# AUDIO_DAC.net
KiCad netlist of a schematic drawn in Altium Designer
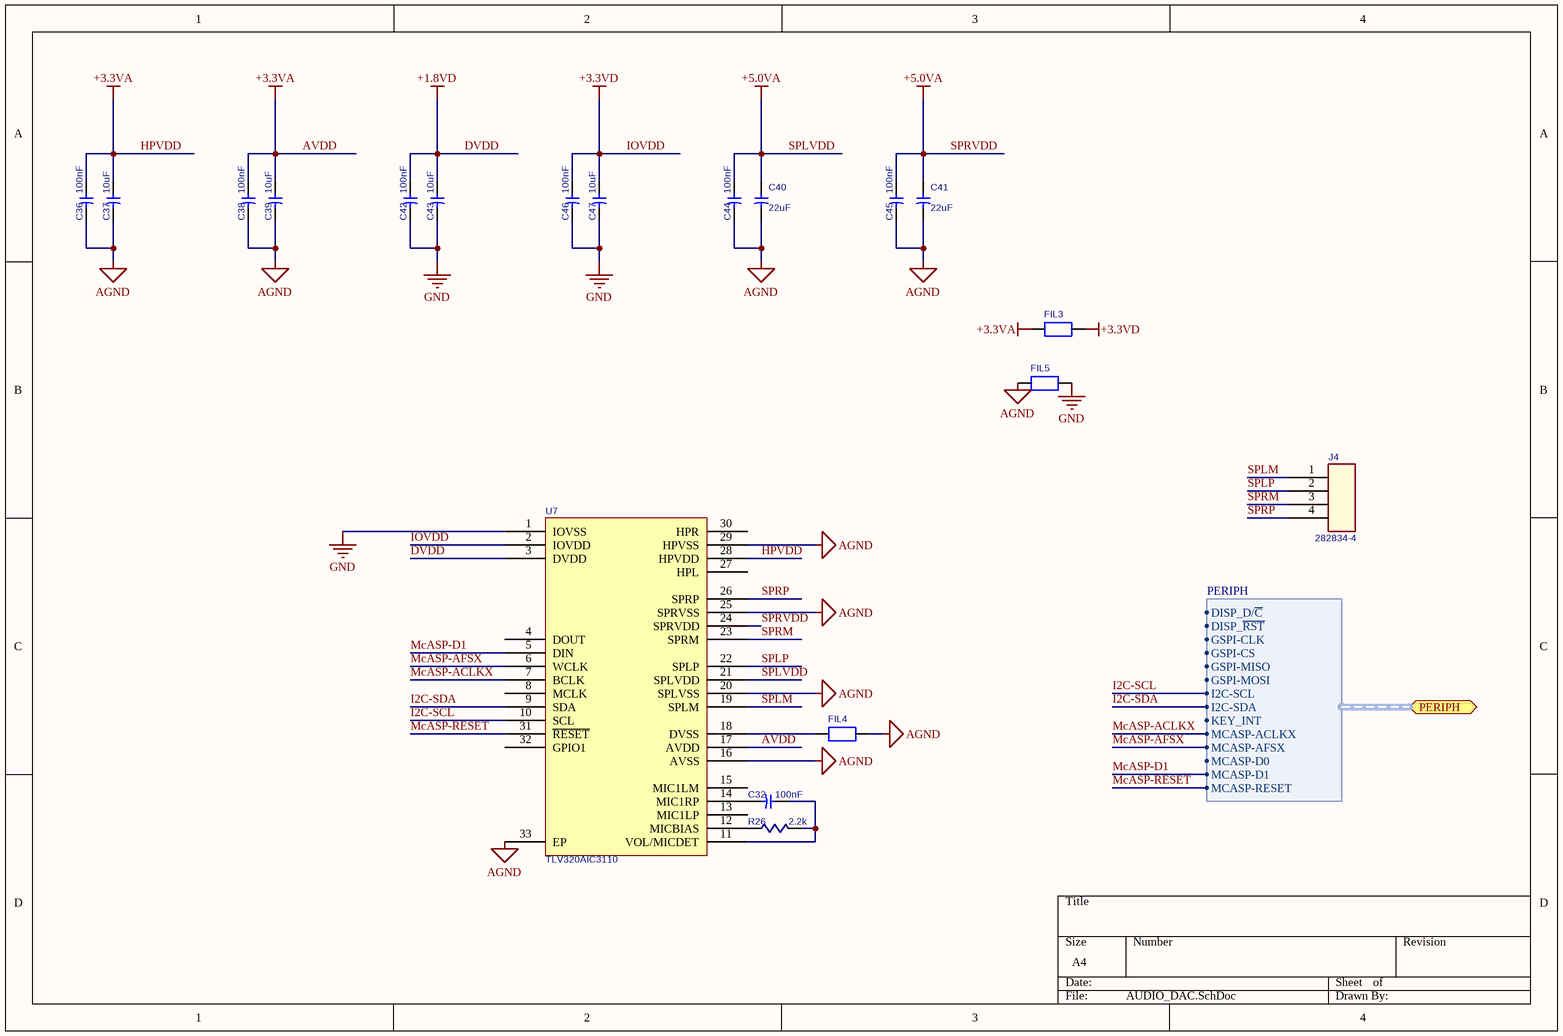
[diagram p0: AUDIO_DAC.SchDoc]

(export (version "E")
  (design (tool "Eeschema 10.0.6"))
  (components
    (comp (ref "C32") (value "100nF") (footprint "C_0603A") (libsource (lib "WiFi_3200") (part "C_0603")))
    (comp (ref "C36") (value "100nF") (footprint "C_0603A") (libsource (lib "WiFi_3200") (part "C_0603")))
    (comp (ref "C37") (value "10uF") (footprint "C_0603A") (libsource (lib "WiFi_3200") (part "C_0603")))
    (comp (ref "C38") (value "100nF") (footprint "C_0603A") (libsource (lib "WiFi_3200") (part "C_0603")))
    (comp (ref "C39") (value "10uF") (footprint "C_0603A") (libsource (lib "WiFi_3200") (part "C_0603")))
    (comp (ref "C40") (value "22uF") (footprint "C_1210D") (libsource (lib "WiFi_3200") (part "C_1210")))
    (comp (ref "C41") (value "22uF") (footprint "C_1210D") (libsource (lib "WiFi_3200") (part "C_1210")))
    (comp (ref "C42") (value "100nF") (footprint "C_0603A") (libsource (lib "WiFi_3200") (part "C_0603")))
    (comp (ref "C43") (value "10uF") (footprint "C_0603A") (libsource (lib "WiFi_3200") (part "C_0603")))
    (comp (ref "C44") (value "100nF") (footprint "C_0603A") (libsource (lib "WiFi_3200") (part "C_0603")))
    (comp (ref "C45") (value "100nF") (footprint "C_0603A") (libsource (lib "WiFi_3200") (part "C_0603")))
    (comp (ref "C46") (value "100nF") (footprint "C_0603A") (libsource (lib "WiFi_3200") (part "C_0603")))
    (comp (ref "C47") (value "10uF") (footprint "C_0603A") (libsource (lib "WiFi_3200") (part "C_0603")))
    (comp (ref "FIL3")
      (value "FB")
      (footprint "FB_0603")
      (fields
        (field (name "MANUFACTURER PART NUMBER") "MPZ1608S221ATA00")
        (field (name "MANUFACTURER") "TDK Corporation")
      )
      (libsource (lib "WiFi_3200") (part "FB_0603"))
    )
    (comp (ref "FIL4")
      (value "FB")
      (footprint "FB_0603")
      (fields
        (field (name "MANUFACTURER PART NUMBER") "MPZ1608S221ATA00")
        (field (name "MANUFACTURER") "TDK Corporation")
      )
      (libsource (lib "WiFi_3200") (part "FB_0603"))
    )
    (comp (ref "FIL5")
      (value "FB")
      (footprint "FB_0603")
      (fields
        (field (name "MANUFACTURER PART NUMBER") "MPZ1608S221ATA00")
        (field (name "MANUFACTURER") "TDK Corporation")
      )
      (libsource (lib "WiFi_3200") (part "FB_0603"))
    )
    (comp (ref "J4")
      (value "282834-4")
      (footprint "HEADER_2.54_SCREW_4PIN")
      (fields (field (name "MANUFACTURER") "TE CONNECTIVITY / BUCHANAN"))
      (libsource (lib "WiFi_3200") (part "TERM_LIST_4"))
    )
    (comp (ref "R26") (value "2.2k") (footprint "R_0603") (libsource (lib "WiFi_3200") (part "R_0603")))
    (comp (ref "U7")
      (value "TLV320AIC3110")
      (footprint "QFN50P500X500X80-32N")
      (fields
        (field (name "MANUFACTURER") "Texas Instruments")
        (field (name "MANUFACTURER PART NUMBER") "TLV320AIC3110IRHBR")
      )
      (libsource (lib "WiFi_3200") (part "TLV320AIC3110"))
    )
  )
  (nets
    (net (code "2") (name "+1.8VD") (class "Default")
      (node (ref "C42") (pin "1") (pinfunction "1_1") (pintype "passive"))
      (node (ref "C43") (pin "1") (pinfunction "1_1") (pintype "passive"))
      (node (ref "U7") (pin "3") (pinfunction "DVDD_3") (pintype "passive"))
    )
    (net (code "3") (name "+3.3VA") (class "Default")
      (node (ref "C36") (pin "1") (pinfunction "1_1") (pintype "passive"))
      (node (ref "C37") (pin "1") (pinfunction "1_1") (pintype "passive"))
      (node (ref "C38") (pin "1") (pinfunction "1_1") (pintype "passive"))
      (node (ref "C39") (pin "1") (pinfunction "1_1") (pintype "passive"))
      (node (ref "FIL3") (pin "2") (pinfunction "2_2") (pintype "passive"))
      (node (ref "U7") (pin "17") (pinfunction "AVDD_17") (pintype "passive"))
      (node (ref "U7") (pin "28") (pinfunction "HPVDD_28") (pintype "passive"))
    )
    (net (code "4") (name "+3.3VD") (class "Default")
      (node (ref "C46") (pin "1") (pinfunction "1_1") (pintype "passive"))
      (node (ref "C47") (pin "1") (pinfunction "1_1") (pintype "passive"))
      (node (ref "FIL3") (pin "1") (pinfunction "1_1") (pintype "passive"))
      (node (ref "U7") (pin "2") (pinfunction "IOVDD_2") (pintype "passive"))
    )
    (net (code "5") (name "+5.0VA") (class "Default")
      (node (ref "C40") (pin "1") (pinfunction "1_1") (pintype "passive"))
      (node (ref "C41") (pin "1") (pinfunction "1_1") (pintype "passive"))
      (node (ref "C44") (pin "1") (pinfunction "1_1") (pintype "passive"))
      (node (ref "C45") (pin "1") (pinfunction "1_1") (pintype "passive"))
      (node (ref "U7") (pin "21") (pinfunction "SPLVDD_21") (pintype "passive"))
      (node (ref "U7") (pin "24") (pinfunction "SPRVDD_24") (pintype "passive"))
    )
    (net (code "6") (name "/I2C-SCL") (class "Default")
      (node (ref "U7") (pin "10") (pinfunction "SCL_10") (pintype "passive"))
    )
    (net (code "7") (name "/I2C-SDA") (class "Default")
      (node (ref "U7") (pin "9") (pinfunction "SDA_9") (pintype "passive"))
    )
    (net (code "8") (name "/McASP-ACLKX") (class "Default")
      (node (ref "U7") (pin "7") (pinfunction "BCLK_7") (pintype "passive"))
    )
    (net (code "9") (name "/McASP-AFSX") (class "Default")
      (node (ref "U7") (pin "6") (pinfunction "WCLK_6") (pintype "passive"))
    )
    (net (code "10") (name "/McASP-D1") (class "Default")
      (node (ref "U7") (pin "5") (pinfunction "DIN_5") (pintype "passive"))
    )
    (net (code "11") (name "/McASP-RESET") (class "Default")
      (node (ref "U7") (pin "31") (pinfunction "~{RESET}_31") (pintype "passive"))
    )
    (net (code "12") (name "/SPLM") (class "Default")
      (node (ref "J4") (pin "1") (pinfunction "1_1") (pintype "passive"))
      (node (ref "U7") (pin "19") (pinfunction "SPLM_19") (pintype "passive"))
    )
    (net (code "13") (name "/SPLP") (class "Default")
      (node (ref "J4") (pin "2") (pinfunction "2_2") (pintype "passive"))
      (node (ref "U7") (pin "22") (pinfunction "SPLP_22") (pintype "passive"))
    )
    (net (code "14") (name "/SPRM") (class "Default")
      (node (ref "J4") (pin "3") (pinfunction "3_3") (pintype "passive"))
      (node (ref "U7") (pin "23") (pinfunction "SPRM_23") (pintype "passive"))
    )
    (net (code "15") (name "/SPRP") (class "Default")
      (node (ref "J4") (pin "4") (pinfunction "4_4") (pintype "passive"))
      (node (ref "U7") (pin "26") (pinfunction "SPRP_26") (pintype "passive"))
    )
    (net (code "17") (name "AGND") (class "Default")
      (node (ref "C36") (pin "2") (pinfunction "2_2") (pintype "passive"))
      (node (ref "C37") (pin "2") (pinfunction "2_2") (pintype "passive"))
      (node (ref "C38") (pin "2") (pinfunction "2_2") (pintype "passive"))
      (node (ref "C39") (pin "2") (pinfunction "2_2") (pintype "passive"))
      (node (ref "C40") (pin "2") (pinfunction "2_2") (pintype "passive"))
      (node (ref "C41") (pin "2") (pinfunction "2_2") (pintype "passive"))
      (node (ref "C44") (pin "2") (pinfunction "2_2") (pintype "passive"))
      (node (ref "C45") (pin "2") (pinfunction "2_2") (pintype "passive"))
      (node (ref "FIL4") (pin "1") (pinfunction "1_1") (pintype "passive"))
      (node (ref "FIL5") (pin "2") (pinfunction "2_2") (pintype "passive"))
      (node (ref "U7") (pin "16") (pinfunction "AVSS_16") (pintype "passive"))
      (node (ref "U7") (pin "20") (pinfunction "SPLVSS_20") (pintype "passive"))
      (node (ref "U7") (pin "25") (pinfunction "SPRVSS_25") (pintype "passive"))
      (node (ref "U7") (pin "29") (pinfunction "HPVSS_29") (pintype "passive"))
      (node (ref "U7") (pin "33") (pinfunction "EP_33") (pintype "passive"))
    )
    (net (code "18") (name "GND") (class "Default")
      (node (ref "C42") (pin "2") (pinfunction "2_2") (pintype "passive"))
      (node (ref "C43") (pin "2") (pinfunction "2_2") (pintype "passive"))
      (node (ref "C46") (pin "2") (pinfunction "2_2") (pintype "passive"))
      (node (ref "C47") (pin "2") (pinfunction "2_2") (pintype "passive"))
      (node (ref "FIL5") (pin "1") (pinfunction "1_1") (pintype "passive"))
      (node (ref "U7") (pin "1") (pinfunction "IOVSS_1") (pintype "passive"))
    )
    (net (code "19") (name "Net-(U7-DVSS)") (class "Default")
      (node (ref "FIL4") (pin "2") (pinfunction "2_2") (pintype "passive"))
      (node (ref "U7") (pin "18") (pinfunction "DVSS_18") (pintype "passive"))
    )
    (net (code "20") (name "Net-(U7-MIC1RP)") (class "Default")
      (node (ref "C32") (pin "2") (pinfunction "2_2") (pintype "passive"))
      (node (ref "U7") (pin "14") (pinfunction "MIC1RP_14") (pintype "passive"))
    )
    (net (code "21") (name "Net-(U7-MICBIAS)") (class "Default")
      (node (ref "R26") (pin "2") (pinfunction "2_2") (pintype "passive"))
      (node (ref "U7") (pin "12") (pinfunction "MICBIAS_12") (pintype "passive"))
    )
    (net (code "22") (name "Net-(U7-VOL{slash}MICDET)") (class "Default")
      (node (ref "C32") (pin "1") (pinfunction "1_1") (pintype "passive"))
      (node (ref "R26") (pin "1") (pinfunction "1_1") (pintype "passive"))
      (node (ref "U7") (pin "11") (pinfunction "VOL/MICDET_11") (pintype "passive"))
    )
    (net (code "23") (name "unconnected-(U7-DOUT-Pad4)") (class "Default")
      (node (ref "U7") (pin "4") (pinfunction "DOUT_4") (pintype "passive"))
    )
    (net (code "24") (name "unconnected-(U7-GPIO1-Pad32)") (class "Default")
      (node (ref "U7") (pin "32") (pinfunction "GPIO1_32") (pintype "passive"))
    )
    (net (code "25") (name "unconnected-(U7-HPL-Pad27)") (class "Default")
      (node (ref "U7") (pin "27") (pinfunction "HPL_27") (pintype "passive"))
    )
    (net (code "26") (name "unconnected-(U7-HPR-Pad30)") (class "Default")
      (node (ref "U7") (pin "30") (pinfunction "HPR_30") (pintype "passive"))
    )
    (net (code "27") (name "unconnected-(U7-MCLK-Pad8)") (class "Default")
      (node (ref "U7") (pin "8") (pinfunction "MCLK_8") (pintype "passive"))
    )
    (net (code "28") (name "unconnected-(U7-MIC1LM-Pad15)") (class "Default")
      (node (ref "U7") (pin "15") (pinfunction "MIC1LM_15") (pintype "passive"))
    )
    (net (code "29") (name "unconnected-(U7-MIC1LP-Pad13)") (class "Default")
      (node (ref "U7") (pin "13") (pinfunction "MIC1LP_13") (pintype "passive"))
    )
  )
)
